# controller.net
KiCad netlist of a schematic drawn in Altium Designer
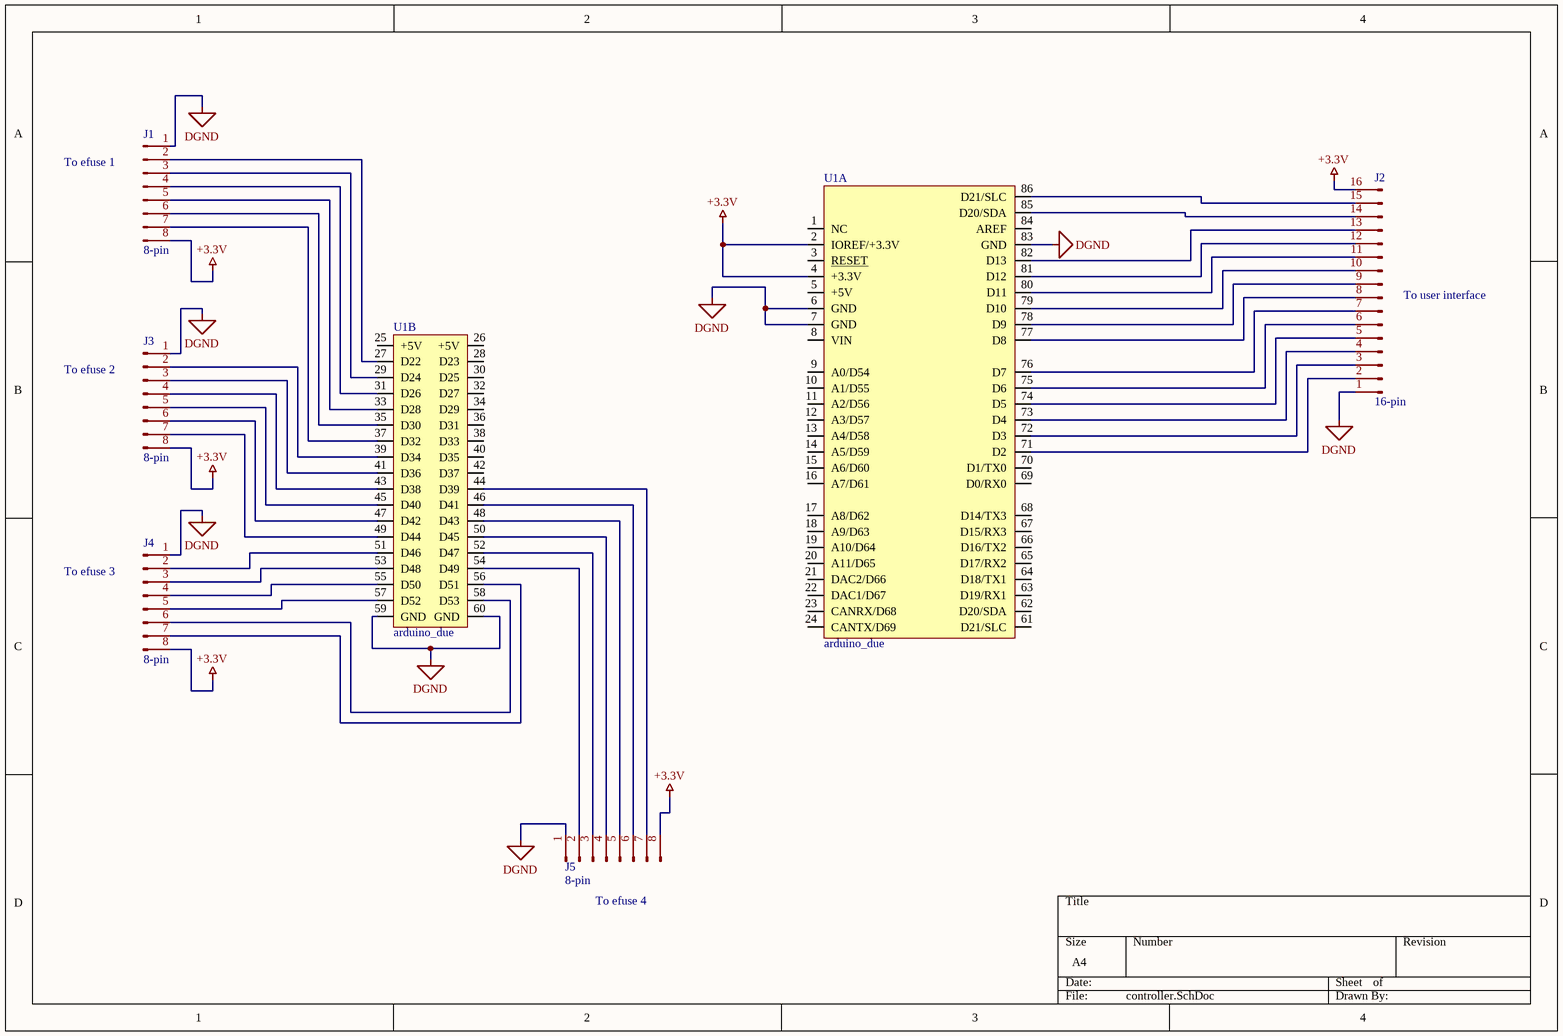
[diagram p0: controller.SchDoc]

(export (version "E")
  (design (tool "Eeschema 10.0.6"))
  (components
    (comp (ref "J1")
      (value "8-pin")
      (footprint "JST_XH_B8B-XH-A_1x08_P2.50mm_Vertical")
      (libsource (lib "JST") (part "8-pin"))
    )
    (comp (ref "J2")
      (value "16-pin")
      (footprint "JST_XH_B16B-XH-A_1x16_P2.50mm_Vertical")
      (libsource (lib "JST") (part "16-pin"))
    )
    (comp (ref "J3")
      (value "8-pin")
      (footprint "JST_XH_B8B-XH-A_1x08_P2.50mm_Vertical")
      (libsource (lib "JST") (part "8-pin"))
    )
    (comp (ref "J4")
      (value "8-pin")
      (footprint "JST_XH_B8B-XH-A_1x08_P2.50mm_Vertical")
      (libsource (lib "JST") (part "8-pin"))
    )
    (comp (ref "J5")
      (value "8-pin")
      (footprint "JST_XH_B8B-XH-A_1x08_P2.50mm_Vertical")
      (libsource (lib "") (part "8-pin_1"))
    )
    (comp (ref "U1")
      (value "arduino_due")
      (footprint "ARDUINO_DUE")
      (libsource (lib "atmel") (part "arduino_due"))
    )
  )
  (nets
    (net (code "1") (name "+3.3V") (class "Default")
      (node (ref "J1") (pin "8") (pinfunction "Pin_8_8") (pintype "passive"))
      (node (ref "J2") (pin "16") (pinfunction "Pin_16_16") (pintype "passive"))
      (node (ref "J3") (pin "8") (pinfunction "Pin_8_8") (pintype "passive"))
      (node (ref "J4") (pin "8") (pinfunction "Pin_8_8") (pintype "passive"))
      (node (ref "J5") (pin "8") (pinfunction "Pin_8_8") (pintype "passive"))
      (node (ref "U1") (pin "2") (pinfunction "IOREF/+3.3V_2") (pintype "passive"))
      (node (ref "U1") (pin "4") (pinfunction "+3.3V_4") (pintype "passive"))
    )
    (net (code "2") (name "DGND") (class "Default")
      (node (ref "J1") (pin "1") (pinfunction "Pin_1_1") (pintype "passive"))
      (node (ref "J2") (pin "1") (pinfunction "Pin_1_1") (pintype "passive"))
      (node (ref "J3") (pin "1") (pinfunction "Pin_1_1") (pintype "passive"))
      (node (ref "J4") (pin "1") (pinfunction "Pin_1_1") (pintype "passive"))
      (node (ref "J5") (pin "1") (pinfunction "Pin_1_1") (pintype "passive"))
      (node (ref "U1") (pin "59") (pinfunction "GND_59") (pintype "passive"))
      (node (ref "U1") (pin "6") (pinfunction "GND_6") (pintype "passive"))
      (node (ref "U1") (pin "60") (pinfunction "GND_60") (pintype "passive"))
      (node (ref "U1") (pin "7") (pinfunction "GND_7") (pintype "passive"))
      (node (ref "U1") (pin "83") (pinfunction "GND_83") (pintype "passive"))
    )
    (net (code "3") (name "Net-(J1-Pin_2)") (class "Default")
      (node (ref "J1") (pin "2") (pinfunction "Pin_2_2") (pintype "passive"))
      (node (ref "U1") (pin "27") (pinfunction "D22_27") (pintype "passive"))
    )
    (net (code "4") (name "Net-(J1-Pin_3)") (class "Default")
      (node (ref "J1") (pin "3") (pinfunction "Pin_3_3") (pintype "passive"))
      (node (ref "U1") (pin "29") (pinfunction "D24_29") (pintype "passive"))
    )
    (net (code "5") (name "Net-(J1-Pin_4)") (class "Default")
      (node (ref "J1") (pin "4") (pinfunction "Pin_4_4") (pintype "passive"))
      (node (ref "U1") (pin "31") (pinfunction "D26_31") (pintype "passive"))
    )
    (net (code "6") (name "Net-(J1-Pin_5)") (class "Default")
      (node (ref "J1") (pin "5") (pinfunction "Pin_5_5") (pintype "passive"))
      (node (ref "U1") (pin "33") (pinfunction "D28_33") (pintype "passive"))
    )
    (net (code "7") (name "Net-(J1-Pin_6)") (class "Default")
      (node (ref "J1") (pin "6") (pinfunction "Pin_6_6") (pintype "passive"))
      (node (ref "U1") (pin "35") (pinfunction "D30_35") (pintype "passive"))
    )
    (net (code "8") (name "Net-(J1-Pin_7)") (class "Default")
      (node (ref "J1") (pin "7") (pinfunction "Pin_7_7") (pintype "passive"))
      (node (ref "U1") (pin "37") (pinfunction "D32_37") (pintype "passive"))
    )
    (net (code "9") (name "Net-(J2-Pin_2)") (class "Default")
      (node (ref "J2") (pin "2") (pinfunction "Pin_2_2") (pintype "passive"))
      (node (ref "U1") (pin "71") (pinfunction "D2_71") (pintype "passive"))
    )
    (net (code "10") (name "Net-(J2-Pin_3)") (class "Default")
      (node (ref "J2") (pin "3") (pinfunction "Pin_3_3") (pintype "passive"))
      (node (ref "U1") (pin "72") (pinfunction "D3_72") (pintype "passive"))
    )
    (net (code "11") (name "Net-(J2-Pin_4)") (class "Default")
      (node (ref "J2") (pin "4") (pinfunction "Pin_4_4") (pintype "passive"))
      (node (ref "U1") (pin "73") (pinfunction "D4_73") (pintype "passive"))
    )
    (net (code "12") (name "Net-(J2-Pin_5)") (class "Default")
      (node (ref "J2") (pin "5") (pinfunction "Pin_5_5") (pintype "passive"))
      (node (ref "U1") (pin "74") (pinfunction "D5_74") (pintype "passive"))
    )
    (net (code "13") (name "Net-(J2-Pin_6)") (class "Default")
      (node (ref "J2") (pin "6") (pinfunction "Pin_6_6") (pintype "passive"))
      (node (ref "U1") (pin "75") (pinfunction "D6_75") (pintype "passive"))
    )
    (net (code "14") (name "Net-(J2-Pin_7)") (class "Default")
      (node (ref "J2") (pin "7") (pinfunction "Pin_7_7") (pintype "passive"))
      (node (ref "U1") (pin "76") (pinfunction "D7_76") (pintype "passive"))
    )
    (net (code "15") (name "Net-(J2-Pin_8)") (class "Default")
      (node (ref "J2") (pin "8") (pinfunction "Pin_8_8") (pintype "passive"))
      (node (ref "U1") (pin "77") (pinfunction "D8_77") (pintype "passive"))
    )
    (net (code "16") (name "Net-(J2-Pin_9)") (class "Default")
      (node (ref "J2") (pin "9") (pinfunction "Pin_9_9") (pintype "passive"))
      (node (ref "U1") (pin "78") (pinfunction "D9_78") (pintype "passive"))
    )
    (net (code "17") (name "Net-(J2-Pin_10)") (class "Default")
      (node (ref "J2") (pin "10") (pinfunction "Pin_10_10") (pintype "passive"))
      (node (ref "U1") (pin "79") (pinfunction "D10_79") (pintype "passive"))
    )
    (net (code "18") (name "Net-(J2-Pin_11)") (class "Default")
      (node (ref "J2") (pin "11") (pinfunction "Pin_11_11") (pintype "passive"))
      (node (ref "U1") (pin "80") (pinfunction "D11_80") (pintype "passive"))
    )
    (net (code "19") (name "Net-(J2-Pin_12)") (class "Default")
      (node (ref "J2") (pin "12") (pinfunction "Pin_12_12") (pintype "passive"))
      (node (ref "U1") (pin "81") (pinfunction "D12_81") (pintype "passive"))
    )
    (net (code "20") (name "Net-(J2-Pin_13)") (class "Default")
      (node (ref "J2") (pin "13") (pinfunction "Pin_13_13") (pintype "passive"))
      (node (ref "U1") (pin "82") (pinfunction "D13_82") (pintype "passive"))
    )
    (net (code "21") (name "Net-(J2-Pin_14)") (class "Default")
      (node (ref "J2") (pin "14") (pinfunction "Pin_14_14") (pintype "passive"))
      (node (ref "U1") (pin "85") (pinfunction "D20/SDA_85") (pintype "passive"))
    )
    (net (code "22") (name "Net-(J2-Pin_15)") (class "Default")
      (node (ref "J2") (pin "15") (pinfunction "Pin_15_15") (pintype "passive"))
      (node (ref "U1") (pin "86") (pinfunction "D21/SLC_86") (pintype "passive"))
    )
    (net (code "23") (name "Net-(J3-Pin_2)") (class "Default")
      (node (ref "J3") (pin "2") (pinfunction "Pin_2_2") (pintype "passive"))
      (node (ref "U1") (pin "39") (pinfunction "D34_39") (pintype "passive"))
    )
    (net (code "24") (name "Net-(J3-Pin_3)") (class "Default")
      (node (ref "J3") (pin "3") (pinfunction "Pin_3_3") (pintype "passive"))
      (node (ref "U1") (pin "41") (pinfunction "D36_41") (pintype "passive"))
    )
    (net (code "25") (name "Net-(J3-Pin_4)") (class "Default")
      (node (ref "J3") (pin "4") (pinfunction "Pin_4_4") (pintype "passive"))
      (node (ref "U1") (pin "43") (pinfunction "D38_43") (pintype "passive"))
    )
    (net (code "26") (name "Net-(J3-Pin_5)") (class "Default")
      (node (ref "J3") (pin "5") (pinfunction "Pin_5_5") (pintype "passive"))
      (node (ref "U1") (pin "45") (pinfunction "D40_45") (pintype "passive"))
    )
    (net (code "27") (name "Net-(J3-Pin_6)") (class "Default")
      (node (ref "J3") (pin "6") (pinfunction "Pin_6_6") (pintype "passive"))
      (node (ref "U1") (pin "47") (pinfunction "D42_47") (pintype "passive"))
    )
    (net (code "28") (name "Net-(J3-Pin_7)") (class "Default")
      (node (ref "J3") (pin "7") (pinfunction "Pin_7_7") (pintype "passive"))
      (node (ref "U1") (pin "49") (pinfunction "D44_49") (pintype "passive"))
    )
    (net (code "29") (name "Net-(J4-Pin_2)") (class "Default")
      (node (ref "J4") (pin "2") (pinfunction "Pin_2_2") (pintype "passive"))
      (node (ref "U1") (pin "51") (pinfunction "D46_51") (pintype "passive"))
    )
    (net (code "30") (name "Net-(J4-Pin_3)") (class "Default")
      (node (ref "J4") (pin "3") (pinfunction "Pin_3_3") (pintype "passive"))
      (node (ref "U1") (pin "53") (pinfunction "D48_53") (pintype "passive"))
    )
    (net (code "31") (name "Net-(J4-Pin_4)") (class "Default")
      (node (ref "J4") (pin "4") (pinfunction "Pin_4_4") (pintype "passive"))
      (node (ref "U1") (pin "55") (pinfunction "D50_55") (pintype "passive"))
    )
    (net (code "32") (name "Net-(J4-Pin_5)") (class "Default")
      (node (ref "J4") (pin "5") (pinfunction "Pin_5_5") (pintype "passive"))
      (node (ref "U1") (pin "57") (pinfunction "D52_57") (pintype "passive"))
    )
    (net (code "33") (name "Net-(J4-Pin_6)") (class "Default")
      (node (ref "J4") (pin "6") (pinfunction "Pin_6_6") (pintype "passive"))
      (node (ref "U1") (pin "58") (pinfunction "D53_58") (pintype "passive"))
    )
    (net (code "34") (name "Net-(J4-Pin_7)") (class "Default")
      (node (ref "J4") (pin "7") (pinfunction "Pin_7_7") (pintype "passive"))
      (node (ref "U1") (pin "56") (pinfunction "D51_56") (pintype "passive"))
    )
    (net (code "35") (name "Net-(J5-Pin_2)") (class "Default")
      (node (ref "J5") (pin "2") (pinfunction "Pin_2_2") (pintype "passive"))
      (node (ref "U1") (pin "54") (pinfunction "D49_54") (pintype "passive"))
    )
    (net (code "36") (name "Net-(J5-Pin_3)") (class "Default")
      (node (ref "J5") (pin "3") (pinfunction "Pin_3_3") (pintype "passive"))
      (node (ref "U1") (pin "52") (pinfunction "D47_52") (pintype "passive"))
    )
    (net (code "37") (name "Net-(J5-Pin_4)") (class "Default")
      (node (ref "J5") (pin "4") (pinfunction "Pin_4_4") (pintype "passive"))
      (node (ref "U1") (pin "50") (pinfunction "D45_50") (pintype "passive"))
    )
    (net (code "38") (name "Net-(J5-Pin_5)") (class "Default")
      (node (ref "J5") (pin "5") (pinfunction "Pin_5_5") (pintype "passive"))
      (node (ref "U1") (pin "48") (pinfunction "D43_48") (pintype "passive"))
    )
    (net (code "39") (name "Net-(J5-Pin_6)") (class "Default")
      (node (ref "J5") (pin "6") (pinfunction "Pin_6_6") (pintype "passive"))
      (node (ref "U1") (pin "46") (pinfunction "D41_46") (pintype "passive"))
    )
    (net (code "40") (name "Net-(J5-Pin_7)") (class "Default")
      (node (ref "J5") (pin "7") (pinfunction "Pin_7_7") (pintype "passive"))
      (node (ref "U1") (pin "44") (pinfunction "D39_44") (pintype "passive"))
    )
    (net (code "41") (name "unconnected-(U1A-+5V-Pad5)") (class "Default")
      (node (ref "U1") (pin "5") (pinfunction "+5V_5") (pintype "passive"))
    )
    (net (code "42") (name "unconnected-(U1A-A0{slash}D54-Pad9)") (class "Default")
      (node (ref "U1") (pin "9") (pinfunction "A0/D54_9") (pintype "passive"))
    )
    (net (code "43") (name "unconnected-(U1A-A1{slash}D55-Pad10)") (class "Default")
      (node (ref "U1") (pin "10") (pinfunction "A1/D55_10") (pintype "passive"))
    )
    (net (code "44") (name "unconnected-(U1A-A2{slash}D56-Pad11)") (class "Default")
      (node (ref "U1") (pin "11") (pinfunction "A2/D56_11") (pintype "passive"))
    )
    (net (code "45") (name "unconnected-(U1A-A3{slash}D57-Pad12)") (class "Default")
      (node (ref "U1") (pin "12") (pinfunction "A3/D57_12") (pintype "passive"))
    )
    (net (code "46") (name "unconnected-(U1A-A4{slash}D58-Pad13)") (class "Default")
      (node (ref "U1") (pin "13") (pinfunction "A4/D58_13") (pintype "passive"))
    )
    (net (code "47") (name "unconnected-(U1A-A5{slash}D59-Pad14)") (class "Default")
      (node (ref "U1") (pin "14") (pinfunction "A5/D59_14") (pintype "passive"))
    )
    (net (code "48") (name "unconnected-(U1A-A6{slash}D60-Pad15)") (class "Default")
      (node (ref "U1") (pin "15") (pinfunction "A6/D60_15") (pintype "passive"))
    )
    (net (code "49") (name "unconnected-(U1A-A7{slash}D61-Pad16)") (class "Default")
      (node (ref "U1") (pin "16") (pinfunction "A7/D61_16") (pintype "passive"))
    )
    (net (code "50") (name "unconnected-(U1A-A8{slash}D62-Pad17)") (class "Default")
      (node (ref "U1") (pin "17") (pinfunction "A8/D62_17") (pintype "passive"))
    )
    (net (code "51") (name "unconnected-(U1A-A9{slash}D63-Pad18)") (class "Default")
      (node (ref "U1") (pin "18") (pinfunction "A9/D63_18") (pintype "passive"))
    )
    (net (code "52") (name "unconnected-(U1A-A10{slash}D64-Pad19)") (class "Default")
      (node (ref "U1") (pin "19") (pinfunction "A10/D64_19") (pintype "passive"))
    )
    (net (code "53") (name "unconnected-(U1A-A11{slash}D65-Pad20)") (class "Default")
      (node (ref "U1") (pin "20") (pinfunction "A11/D65_20") (pintype "passive"))
    )
    (net (code "54") (name "unconnected-(U1A-AREF-Pad84)") (class "Default")
      (node (ref "U1") (pin "84") (pinfunction "AREF_84") (pintype "passive"))
    )
    (net (code "55") (name "unconnected-(U1A-CANRX{slash}D68-Pad23)") (class "Default")
      (node (ref "U1") (pin "23") (pinfunction "CANRX/D68_23") (pintype "passive"))
    )
    (net (code "56") (name "unconnected-(U1A-CANTX{slash}D69-Pad24)") (class "Default")
      (node (ref "U1") (pin "24") (pinfunction "CANTX/D69_24") (pintype "passive"))
    )
    (net (code "57") (name "unconnected-(U1A-D0{slash}RX0-Pad69)") (class "Default")
      (node (ref "U1") (pin "69") (pinfunction "D0/RX0_69") (pintype "passive"))
    )
    (net (code "58") (name "unconnected-(U1A-D1{slash}TX0-Pad70)") (class "Default")
      (node (ref "U1") (pin "70") (pinfunction "D1/TX0_70") (pintype "passive"))
    )
    (net (code "59") (name "unconnected-(U1A-D14{slash}TX3-Pad68)") (class "Default")
      (node (ref "U1") (pin "68") (pinfunction "D14/TX3_68") (pintype "passive"))
    )
    (net (code "60") (name "unconnected-(U1A-D15{slash}RX3-Pad67)") (class "Default")
      (node (ref "U1") (pin "67") (pinfunction "D15/RX3_67") (pintype "passive"))
    )
    (net (code "61") (name "unconnected-(U1A-D16{slash}TX2-Pad66)") (class "Default")
      (node (ref "U1") (pin "66") (pinfunction "D16/TX2_66") (pintype "passive"))
    )
    (net (code "62") (name "unconnected-(U1A-D17{slash}RX2-Pad65)") (class "Default")
      (node (ref "U1") (pin "65") (pinfunction "D17/RX2_65") (pintype "passive"))
    )
    (net (code "63") (name "unconnected-(U1A-D18{slash}TX1-Pad64)") (class "Default")
      (node (ref "U1") (pin "64") (pinfunction "D18/TX1_64") (pintype "passive"))
    )
    (net (code "64") (name "unconnected-(U1A-D19{slash}RX1-Pad63)") (class "Default")
      (node (ref "U1") (pin "63") (pinfunction "D19/RX1_63") (pintype "passive"))
    )
    (net (code "65") (name "unconnected-(U1A-D20{slash}SDA-Pad62)") (class "Default")
      (node (ref "U1") (pin "62") (pinfunction "D20/SDA_62") (pintype "passive"))
    )
    (net (code "66") (name "unconnected-(U1A-D21{slash}SLC-Pad61)") (class "Default")
      (node (ref "U1") (pin "61") (pinfunction "D21/SLC_61") (pintype "passive"))
    )
    (net (code "67") (name "unconnected-(U1A-DAC1{slash}D67-Pad22)") (class "Default")
      (node (ref "U1") (pin "22") (pinfunction "DAC1/D67_22") (pintype "passive"))
    )
    (net (code "68") (name "unconnected-(U1A-DAC2{slash}D66-Pad21)") (class "Default")
      (node (ref "U1") (pin "21") (pinfunction "DAC2/D66_21") (pintype "passive"))
    )
    (net (code "69") (name "unconnected-(U1A-NC-Pad1)") (class "Default")
      (node (ref "U1") (pin "1") (pinfunction "NC_1") (pintype "passive"))
    )
    (net (code "70") (name "unconnected-(U1A-RESET-Pad3)") (class "Default")
      (node (ref "U1") (pin "3") (pinfunction "RESET_3") (pintype "passive"))
    )
    (net (code "71") (name "unconnected-(U1A-VIN-Pad8)") (class "Default")
      (node (ref "U1") (pin "8") (pinfunction "VIN_8") (pintype "passive"))
    )
    (net (code "72") (name "unconnected-(U1B-+5V-Pad25)") (class "Default")
      (node (ref "U1") (pin "25") (pinfunction "+5V_25") (pintype "passive"))
    )
    (net (code "73") (name "unconnected-(U1B-+5V-Pad26)") (class "Default")
      (node (ref "U1") (pin "26") (pinfunction "+5V_26") (pintype "passive"))
    )
    (net (code "74") (name "unconnected-(U1B-D23-Pad28)") (class "Default")
      (node (ref "U1") (pin "28") (pinfunction "D23_28") (pintype "passive"))
    )
    (net (code "75") (name "unconnected-(U1B-D25-Pad30)") (class "Default")
      (node (ref "U1") (pin "30") (pinfunction "D25_30") (pintype "passive"))
    )
    (net (code "76") (name "unconnected-(U1B-D27-Pad32)") (class "Default")
      (node (ref "U1") (pin "32") (pinfunction "D27_32") (pintype "passive"))
    )
    (net (code "77") (name "unconnected-(U1B-D29-Pad34)") (class "Default")
      (node (ref "U1") (pin "34") (pinfunction "D29_34") (pintype "passive"))
    )
    (net (code "78") (name "unconnected-(U1B-D31-Pad36)") (class "Default")
      (node (ref "U1") (pin "36") (pinfunction "D31_36") (pintype "passive"))
    )
    (net (code "79") (name "unconnected-(U1B-D33-Pad38)") (class "Default")
      (node (ref "U1") (pin "38") (pinfunction "D33_38") (pintype "passive"))
    )
    (net (code "80") (name "unconnected-(U1B-D35-Pad40)") (class "Default")
      (node (ref "U1") (pin "40") (pinfunction "D35_40") (pintype "passive"))
    )
    (net (code "81") (name "unconnected-(U1B-D37-Pad42)") (class "Default")
      (node (ref "U1") (pin "42") (pinfunction "D37_42") (pintype "passive"))
    )
  )
)
